# TopLevel.net
KiCad netlist of a schematic drawn in Altium Designer
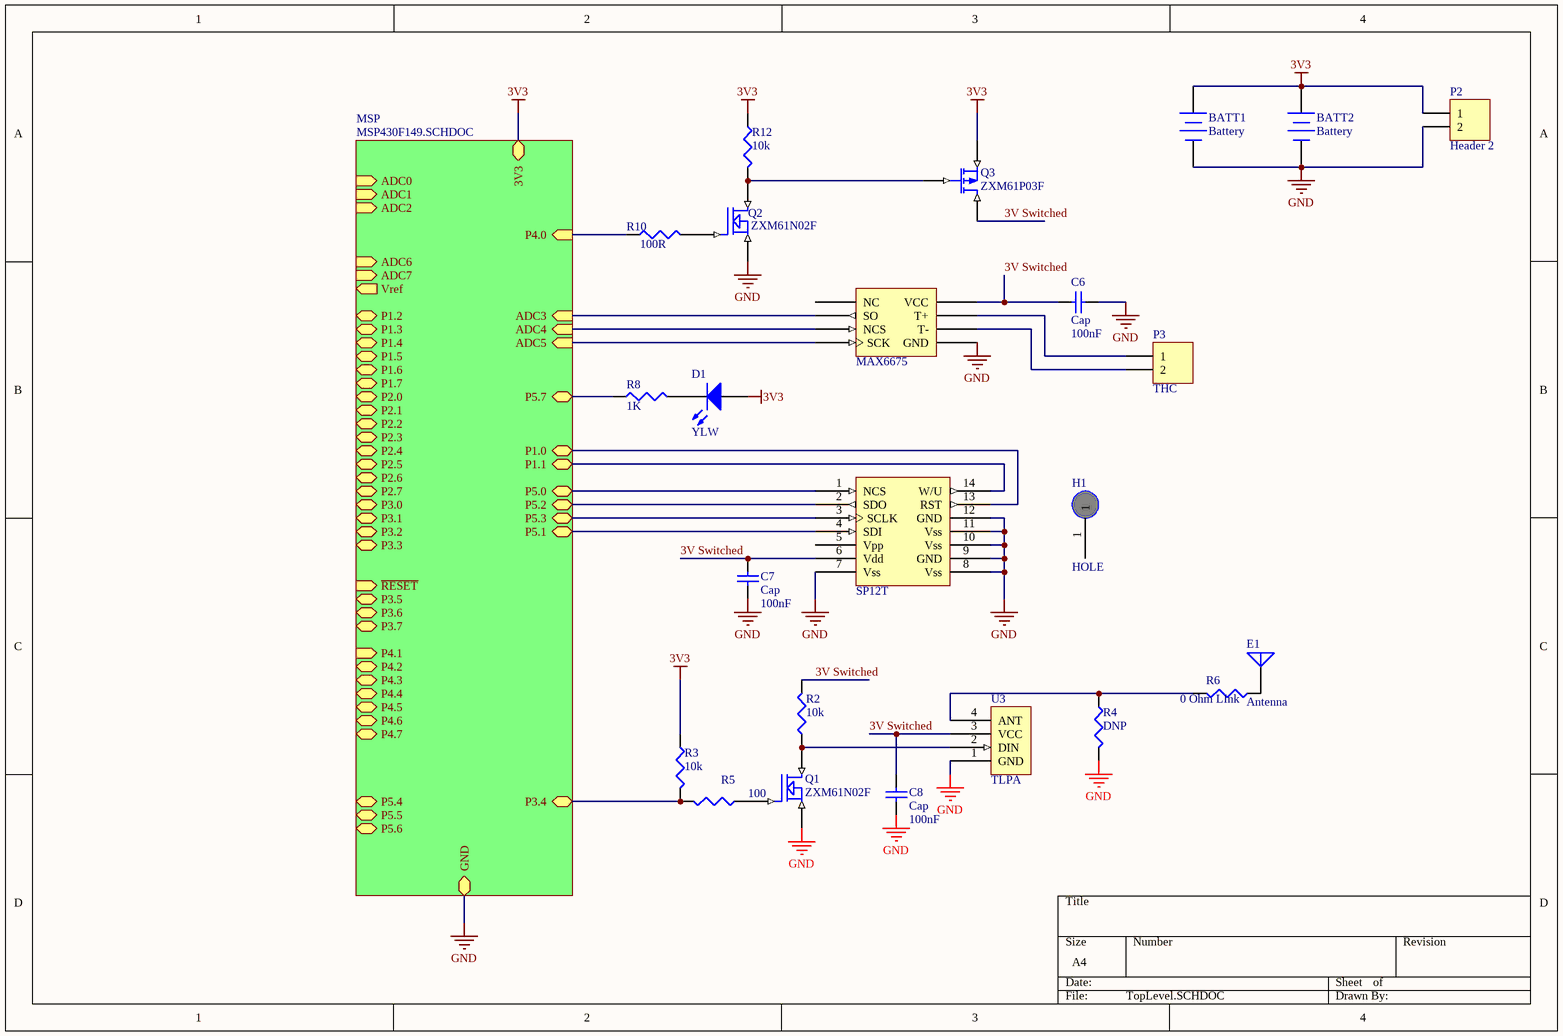
[diagram p0: TopLevel.SCHDOC]

(export (version "E")
  (design (tool "Eeschema 10.0.6"))
  (components
    (comp (ref "BATT1")
      (value "Battery")
      (footprint "Keystone Battery:Keystone CR1632 Holder")
      (description "Multicell Battery")
      (fields (field (name "PUBLISHER") "Altium Limited"))
      (libsource (lib "Miscellaneous Devices") (part "Battery"))
    )
    (comp (ref "BATT2")
      (value "Battery")
      (footprint "Keystone Battery:Keystone CR1632 Holder")
      (description "Multicell Battery")
      (fields (field (name "PUBLISHER") "Altium Limited"))
      (libsource (lib "Miscellaneous Devices") (part "Battery"))
    )
    (comp (ref "C6")
      (value "Cap")
      (footprint "IPC-SM-782 Section 8.2 Chip Capacitor:1608[0603]")
      (description "Capacitor")
      (fields (field (name "ALTIUM_VALUE") "100nF") (field (name "PUBLISHER") "Altium Limited"))
      (libsource (lib "Miscellaneous Devices") (part "Cap"))
    )
    (comp (ref "C7")
      (value "Cap")
      (footprint "IPC-SM-782 Section 8.2 Chip Capacitor:1608[0603]")
      (description "Capacitor")
      (fields (field (name "ALTIUM_VALUE") "100nF") (field (name "PUBLISHER") "Altium Limited"))
      (libsource (lib "Miscellaneous Devices") (part "Cap"))
    )
    (comp (ref "C8")
      (value "Cap")
      (footprint "IPC-SM-782 Section 8.2 Chip Capacitor:1608[0603]")
      (description "Capacitor")
      (fields (field (name "ALTIUM_VALUE") "100nF") (field (name "PUBLISHER") "Altium Limited"))
      (libsource (lib "Miscellaneous Devices") (part "Cap"))
    )
    (comp (ref "D1")
      (value "YLW")
      (footprint "IPC-SM-782 Section 8.1 Chip Resistor:2012[0805]")
      (description "Typical RED GaAs LED")
      (fields (field (name "PUBLISHER") "Altium Limited"))
      (libsource (lib "Miscellaneous Devices") (part "LED1"))
    )
    (comp (ref "E1")
      (value "Antenna")
      (footprint "Miscellaneous Connector PCB:PIN1")
      (description "Generic Antenna")
      (fields (field (name "PUBLISHER") "Altium Limited"))
      (libsource (lib "Miscellaneous Devices") (part "Antenna"))
    )
    (comp (ref "H1")
      (value "HOLE")
      (footprint "M2.5")
      (description "Hole")
      (libsource (lib "Miscellaneous") (part "HOLE"))
    )
    (comp (ref "MAX6675")
      (value "MAX6675")
      (footprint "SO8")
      (description "MAXIM 6675 SPI Thermocouple Amplifier")
      (libsource (lib "MAX6675") (part "MAX6675"))
    )
    (comp (ref "P2")
      (value "Header 2")
      (footprint "HDR1X2")
      (description "Header, 2-Pin")
      (fields (field (name "PUBLISHER") "Altium Limited"))
      (libsource (lib "Miscellaneous Connectors") (part "Header 2"))
    )
    (comp (ref "P3")
      (value "THC")
      (footprint "HDR1X2")
      (description "Header, 2-Pin")
      (fields (field (name "PUBLISHER") "Altium Limited"))
      (libsource (lib "Miscellaneous Connectors") (part "Header 2"))
    )
    (comp (ref "Q1")
      (value "ZXM61N02F")
      (footprint "SOT23")
      (description "1.7A, 20V N-Channel Enhancement mode FET")
      (libsource (lib "RCLDQ") (part "ZXM61N02F"))
    )
    (comp (ref "Q2")
      (value "ZXM61N02F")
      (footprint "SOT23-3")
      (description "1.7A, 20V N-Channel Enhancement mode FET")
      (libsource (lib "") (part "ZXM61N02F_1"))
    )
    (comp (ref "Q3")
      (value "ZXM61P03F")
      (footprint "SOT23-3")
      (description "1.1A, 30V P-Channel Enhancement mode FET")
      (libsource (lib "RCLDQ") (part "ZXM61P03F"))
    )
    (comp (ref "R2")
      (value "10k")
      (footprint "IPC-SM-782 Section 8.1 Chip Resistor:1608[0603]")
      (description "Resistor")
      (libsource (lib "RCLDQ") (part "RES1"))
    )
    (comp (ref "R3")
      (value "10k")
      (footprint "IPC-SM-782 Section 8.1 Chip Resistor:1608[0603]")
      (description "Resistor")
      (libsource (lib "RCLDQ") (part "RES1"))
    )
    (comp (ref "R4")
      (value "DNP")
      (footprint "IPC-SM-782 Section 8.1 Chip Resistor:1608[0603]")
      (description "Resistor")
      (libsource (lib "RCLDQ") (part "RES1"))
    )
    (comp (ref "R5")
      (value "100")
      (footprint "IPC-SM-782 Section 8.1 Chip Resistor:1608[0603]")
      (description "Resistor")
      (libsource (lib "RCLDQ") (part "RES1"))
    )
    (comp (ref "R6")
      (value "0 Ohm LInk")
      (footprint "IPC-SM-782 Section 8.1 Chip Resistor:1608[0603]")
      (description "Resistor")
      (libsource (lib "RCLDQ") (part "RES1"))
    )
    (comp (ref "R8")
      (value "1K")
      (footprint "IPC-SM-782 Section 8.1 Chip Resistor:1608[0603]")
      (description "Resistor")
      (libsource (lib "RCLDQ") (part "RES1"))
    )
    (comp (ref "R10")
      (value "100R")
      (footprint "IPC-SM-782 Section 8.1 Chip Resistor:1608[0603]")
      (description "Resistor")
      (libsource (lib "RCLDQ") (part "RES1"))
    )
    (comp (ref "R12")
      (value "10k")
      (footprint "IPC-SM-782 Section 8.1 Chip Resistor:1608[0603]")
      (description "Resistor")
      (libsource (lib "RCLDQ") (part "RES1"))
    )
    (comp (ref "SP12T")
      (value "SP12T")
      (footprint "SP12T:SOP14")
      (description "Pressure/Temperature sensor")
      (libsource (lib "SP12T") (part "SP12T"))
    )
    (comp (ref "U3") (value "TLPA") (footprint "RF:TLPA Flat") (libsource (lib "RF") (part "TLPA")))
  )
  (nets
    (net (code "1") (name "/3V Switched") (class "Default")
      (node (ref "C6") (pin "1") (pinfunction "1_1") (pintype "passive"))
      (node (ref "C7") (pin "2") (pinfunction "2_2") (pintype "passive"))
      (node (ref "C8") (pin "2") (pinfunction "2_2") (pintype "passive"))
      (node (ref "MAX6675") (pin "4") (pinfunction "VCC_4") (pintype "power_in"))
      (node (ref "Q3") (pin "3") (pinfunction "S_3") (pintype "input"))
      (node (ref "R2") (pin "2") (pinfunction "2_2") (pintype "passive"))
      (node (ref "SP12T") (pin "6") (pinfunction "Vdd_6") (pintype "power_in"))
      (node (ref "U3") (pin "3") (pinfunction "VCC_3") (pintype "power_in"))
    )
    (net (code "5") (name "/ADC3") (class "Default")
      (node (ref "MAX6675") (pin "7") (pinfunction "SO_7") (pintype "output"))
    )
    (net (code "6") (name "/ADC4") (class "Default")
      (node (ref "MAX6675") (pin "6") (pinfunction "NCS_6") (pintype "input"))
    )
    (net (code "7") (name "/ADC5") (class "Default")
      (node (ref "MAX6675") (pin "5") (pinfunction "SCK_5") (pintype "input"))
    )
    (net (code "10") (name "/P1.0") (class "Default")
      (node (ref "SP12T") (pin "13") (pinfunction "RST_13") (pintype "output"))
    )
    (net (code "11") (name "/P1.1") (class "Default")
      (node (ref "SP12T") (pin "14") (pinfunction "W/U_14") (pintype "output"))
    )
    (net (code "30") (name "/P3.4") (class "Default")
      (node (ref "R3") (pin "2") (pinfunction "2_2") (pintype "passive"))
      (node (ref "R5") (pin "2") (pinfunction "2_2") (pintype "passive"))
    )
    (net (code "34") (name "/P4.0") (class "Default")
      (node (ref "R10") (pin "1") (pinfunction "1_1") (pintype "passive"))
    )
    (net (code "42") (name "/P5.0") (class "Default")
      (node (ref "SP12T") (pin "1") (pinfunction "NCS_1") (pintype "input"))
    )
    (net (code "43") (name "/P5.1") (class "Default")
      (node (ref "SP12T") (pin "4") (pinfunction "SDI_4") (pintype "input"))
    )
    (net (code "44") (name "/P5.2") (class "Default")
      (node (ref "SP12T") (pin "2") (pinfunction "SDO_2") (pintype "output"))
    )
    (net (code "45") (name "/P5.3") (class "Default")
      (node (ref "SP12T") (pin "3") (pinfunction "SCLK_3") (pintype "input"))
    )
    (net (code "49") (name "/P5.7") (class "Default")
      (node (ref "R8") (pin "1") (pinfunction "1_1") (pintype "passive"))
    )
    (net (code "52") (name "3V3") (class "Default")
      (node (ref "BATT1") (pin "1") (pinfunction "+_1") (pintype "passive"))
      (node (ref "BATT2") (pin "1") (pinfunction "+_1") (pintype "passive"))
      (node (ref "D1") (pin "1") (pinfunction "A_1") (pintype "passive"))
      (node (ref "P2") (pin "1") (pinfunction "1_1") (pintype "passive"))
      (node (ref "Q3") (pin "2") (pinfunction "D_2") (pintype "input"))
      (node (ref "R12") (pin "1") (pinfunction "1_1") (pintype "passive"))
      (node (ref "R3") (pin "1") (pinfunction "1_1") (pintype "passive"))
    )
    (net (code "53") (name "GND") (class "Default")
      (node (ref "BATT1") (pin "2") (pinfunction "-_2") (pintype "passive"))
      (node (ref "BATT2") (pin "2") (pinfunction "-_2") (pintype "passive"))
      (node (ref "C6") (pin "2") (pinfunction "2_2") (pintype "passive"))
      (node (ref "C7") (pin "1") (pinfunction "1_1") (pintype "passive"))
      (node (ref "C8") (pin "1") (pinfunction "1_1") (pintype "passive"))
      (node (ref "MAX6675") (pin "1") (pinfunction "GND_1") (pintype "power_in"))
      (node (ref "P2") (pin "2") (pinfunction "2_2") (pintype "passive"))
      (node (ref "Q1") (pin "2") (pinfunction "S_2") (pintype "input"))
      (node (ref "Q2") (pin "2") (pinfunction "S_2") (pintype "input"))
      (node (ref "R4") (pin "2") (pinfunction "2_2") (pintype "passive"))
      (node (ref "SP12T") (pin "10") (pinfunction "Vss_10") (pintype "power_in"))
      (node (ref "SP12T") (pin "11") (pinfunction "Vss_11") (pintype "power_in"))
      (node (ref "SP12T") (pin "12") (pinfunction "GND_12") (pintype "power_in"))
      (node (ref "SP12T") (pin "7") (pinfunction "Vss_7") (pintype "power_in"))
      (node (ref "SP12T") (pin "8") (pinfunction "Vss_8") (pintype "power_in"))
      (node (ref "SP12T") (pin "9") (pinfunction "GND_9") (pintype "power_in"))
      (node (ref "U3") (pin "1") (pinfunction "GND_1") (pintype "power_in"))
    )
    (net (code "54") (name "Net-(D1-K)") (class "Default")
      (node (ref "D1") (pin "2") (pinfunction "K_2") (pintype "passive"))
      (node (ref "R8") (pin "2") (pinfunction "2_2") (pintype "passive"))
    )
    (net (code "55") (name "Net-(E1-A)") (class "Default")
      (node (ref "E1") (pin "1") (pinfunction "A_1") (pintype "passive"))
      (node (ref "R6") (pin "1") (pinfunction "1_1") (pintype "passive"))
    )
    (net (code "56") (name "Net-(MAX6675-T+)") (class "Default")
      (node (ref "MAX6675") (pin "3") (pinfunction "T+_3") (pintype "passive"))
      (node (ref "P3") (pin "1") (pinfunction "1_1") (pintype "passive"))
    )
    (net (code "57") (name "Net-(MAX6675-T-)") (class "Default")
      (node (ref "MAX6675") (pin "2") (pinfunction "T-_2") (pintype "passive"))
      (node (ref "P3") (pin "2") (pinfunction "2_2") (pintype "passive"))
    )
    (net (code "58") (name "Net-(Q1-D)") (class "Default")
      (node (ref "Q1") (pin "3") (pinfunction "D_3") (pintype "input"))
      (node (ref "R2") (pin "1") (pinfunction "1_1") (pintype "passive"))
      (node (ref "U3") (pin "2") (pinfunction "DIN_2") (pintype "input"))
    )
    (net (code "59") (name "Net-(Q1-G)") (class "Default")
      (node (ref "Q1") (pin "1") (pinfunction "G_1") (pintype "input"))
      (node (ref "R5") (pin "1") (pinfunction "1_1") (pintype "passive"))
    )
    (net (code "60") (name "Net-(Q2-D)") (class "Default")
      (node (ref "Q2") (pin "3") (pinfunction "D_3") (pintype "input"))
      (node (ref "Q3") (pin "1") (pinfunction "G_1") (pintype "input"))
      (node (ref "R12") (pin "2") (pinfunction "2_2") (pintype "passive"))
    )
    (net (code "61") (name "Net-(Q2-G)") (class "Default")
      (node (ref "Q2") (pin "1") (pinfunction "G_1") (pintype "input"))
      (node (ref "R10") (pin "2") (pinfunction "2_2") (pintype "passive"))
    )
    (net (code "62") (name "Net-(U3-ANT)") (class "Default")
      (node (ref "R4") (pin "1") (pinfunction "1_1") (pintype "passive"))
      (node (ref "R6") (pin "2") (pinfunction "2_2") (pintype "passive"))
      (node (ref "U3") (pin "4") (pinfunction "ANT_4") (pintype "passive"))
    )
    (net (code "63") (name "unconnected-(H1-Pad1)") (class "Default")
      (node (ref "H1") (pin "1") (pinfunction "1_1") (pintype "passive"))
    )
    (net (code "64") (name "unconnected-(MAX6675-NC-Pad8)") (class "Default")
      (node (ref "MAX6675") (pin "8") (pinfunction "NC_8") (pintype "passive"))
    )
    (net (code "65") (name "unconnected-(SP12T-Vpp-Pad5)") (class "Default")
      (node (ref "SP12T") (pin "5") (pinfunction "Vpp_5") (pintype "tri_state"))
    )
  )
)
